# Crystal.net
KiCad netlist of a schematic drawn in Altium Designer
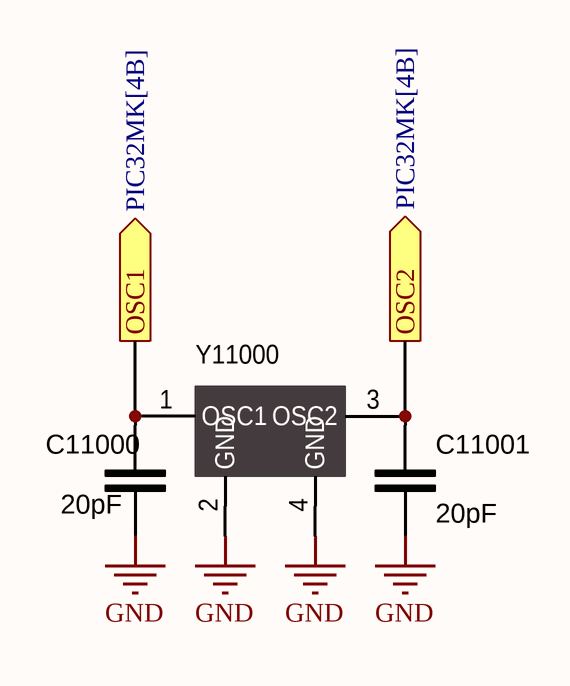
[diagram p0: Crystal.SchDoc]

(export (version "E")
  (design (tool "Eeschema 10.0.6"))
  (components
    (comp (ref "C11000")
      (value "20pF")
      (footprint "CAP_0603")
      (description "CAP CER 100nF 0603 25V X7R")
      (libsource (lib "CapacitorsIntegrated") (part "C000007"))
    )
    (comp (ref "C11001")
      (value "20pF")
      (footprint "CAP_0603")
      (description "CAP CER 100nF 0603 25V X7R")
      (libsource (lib "CapacitorsIntegrated") (part "C000007"))
    )
    (comp (ref "Y11000")
      (value "8Hz")
      (footprint "ABM10")
      (description "CRYSTAL 8.0000MHZ 18PF SMD")
      (fields
        (field (name "MANUFACTURER") "ABRACON")
        (field (name "MANUFACTURER PART NUMBER") "ABMM2-8.000MHZ-E2-T")
      )
      (libsource (lib "motion_board") (part "QUARTZ_8MHz"))
    )
  )
  (nets
    (net (code "1") (name "/OSC1") (class "Default")
      (node (ref "C11000") (pin "1") (pinfunction "1_1") (pintype "passive"))
      (node (ref "Y11000") (pin "1") (pinfunction "OSC1_1") (pintype "passive"))
    )
    (net (code "2") (name "/OSC2") (class "Default")
      (node (ref "C11001") (pin "1") (pinfunction "1_1") (pintype "passive"))
      (node (ref "Y11000") (pin "3") (pinfunction "OSC2_3") (pintype "passive"))
    )
    (net (code "3") (name "GND") (class "Default")
      (node (ref "C11000") (pin "2") (pinfunction "2_2") (pintype "passive"))
      (node (ref "C11001") (pin "2") (pinfunction "2_2") (pintype "passive"))
      (node (ref "Y11000") (pin "2") (pinfunction "GND_2") (pintype "passive"))
      (node (ref "Y11000") (pin "4") (pinfunction "GND_4") (pintype "passive"))
    )
  )
)
